# Power_Board_Schematic_Bad.net
KiCad netlist of a schematic drawn in Altium Designer
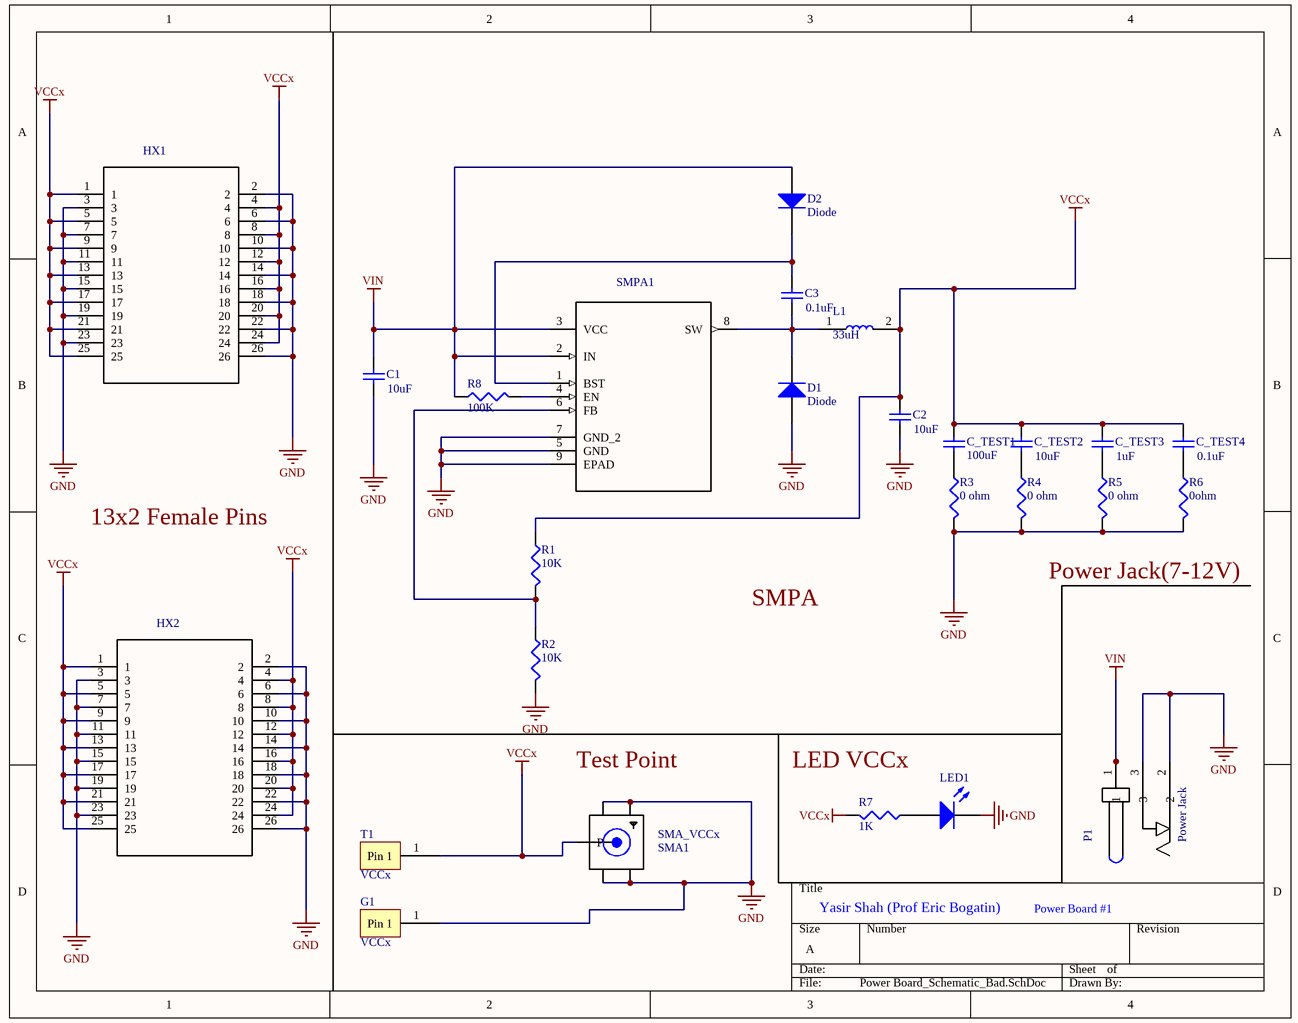
[diagram p0: Power Board_Schematic_Bad.SchDoc]

(export (version "E")
  (design (tool "Eeschema 10.0.6"))
  (components
    (comp (ref "C1")
      (value "10uF")
      (footprint "CAPC2012X140N")
      (description "Capacitor (Semiconductor SIM Model)")
      (fields (field (name "Comment") "Cap Semi") (field (name "PUBLISHER") "Altium Limited"))
      (libsource (lib "Miscellaneous Devices") (part "Cap Semi"))
    )
    (comp (ref "C2")
      (value "10uF")
      (footprint "CAPC2012X140N")
      (description "Capacitor (Semiconductor SIM Model)")
      (fields (field (name "Comment") "Cap Semi") (field (name "PUBLISHER") "Altium Limited"))
      (libsource (lib "Miscellaneous Devices") (part "Cap Semi"))
    )
    (comp (ref "C3")
      (value "0.1uF")
      (footprint "CAPC2012X140N")
      (description "Capacitor (Semiconductor SIM Model)")
      (fields (field (name "Comment") "Cap Semi") (field (name "PUBLISHER") "Altium Limited"))
      (libsource (lib "Miscellaneous Devices") (part "Cap Semi"))
    )
    (comp (ref "C_TEST1")
      (value "100uF")
      (footprint "CAPC2012X140N")
      (description "Capacitor (Semiconductor SIM Model)")
      (fields (field (name "Comment") "Cap Semi") (field (name "PUBLISHER") "Altium Limited"))
      (libsource (lib "Miscellaneous Devices") (part "Cap Semi"))
    )
    (comp (ref "C_TEST2")
      (value "10uF")
      (footprint "CAPC2012X140N")
      (description "Capacitor (Semiconductor SIM Model)")
      (fields (field (name "Comment") "Cap Semi") (field (name "PUBLISHER") "Altium Limited"))
      (libsource (lib "Miscellaneous Devices") (part "Cap Semi"))
    )
    (comp (ref "C_TEST3")
      (value "1uF")
      (footprint "CAPC2012X140N")
      (description "Capacitor (Semiconductor SIM Model)")
      (fields (field (name "Comment") "Cap Semi") (field (name "PUBLISHER") "Altium Limited"))
      (libsource (lib "Miscellaneous Devices") (part "Cap Semi"))
    )
    (comp (ref "C_TEST4")
      (value "0.1uF")
      (footprint "CAPC2012X140N")
      (description "Capacitor (Semiconductor SIM Model)")
      (fields (field (name "Comment") "Cap Semi") (field (name "PUBLISHER") "Altium Limited"))
      (libsource (lib "Miscellaneous Devices") (part "Cap Semi"))
    )
    (comp (ref "D1")
      (value "Diode")
      (footprint "D1")
      (description "Default Diode")
      (fields (field (name "PUBLISHER") "Altium Limited"))
      (libsource (lib "Miscellaneous Devices") (part "Diode"))
    )
    (comp (ref "D2")
      (value "Diode")
      (footprint "d2")
      (description "Default Diode")
      (fields (field (name "PUBLISHER") "Altium Limited"))
      (libsource (lib "Miscellaneous Devices") (part "Diode"))
    )
    (comp (ref "G1")
      (value "VCCx")
      (footprint "PCBComponent_1")
      (libsource (lib "SchematicLibrary") (part "1Pin Header"))
    )
    (comp (ref "HX1")
      (value "~")
      (footprint "TYCO_1761606-9")
      (description "Header, Pin, Idc, Amp-Latch, 26 Pos, Low Profile, Pcb, Vertical, Black")
      (fields (field (name "MF") "TE Connectivity") (field (name "MP") "1761606-9"))
      (libsource (lib "1761606-9") (part "1761606-9"))
    )
    (comp (ref "HX2")
      (value "~")
      (footprint "TYCO_1761606-9")
      (description "Header, Pin, Idc, Amp-Latch, 26 Pos, Low Profile, Pcb, Vertical, Black")
      (fields (field (name "MF") "TE Connectivity") (field (name "MP") "1761606-9"))
      (libsource (lib "1761606-9") (part "1761606-9"))
    )
    (comp (ref "L1")
      (value "33uH")
      (footprint "CAPC2012X140N")
      (description "Inductor Power Shielded Multi-Layer 2.2uH 20% 2MHz Ferrite 1A 195mOhm DCR 0805 Punched Paper T/R")
      (fields (field (name "MF") "TDK") (field (name "MP") "MLP2012H2R2MT0S1"))
      (libsource (lib "MLP2012H2R2MT0S1") (part "MLP2012H2R2MT0S1"))
    )
    (comp (ref "LED1")
      (value "LED2")
      (footprint "C1206")
      (description "Typical RED, GREEN, YELLOW, AMBER GaAs LED")
      (fields (field (name "PUBLISHER") "Altium Limited"))
      (libsource (lib "Miscellaneous Devices") (part "LED2"))
    )
    (comp (ref "P1")
      (value "Power Jack")
      (footprint "CUI_PJ-002AH-SMT-TR")
      (description "24 VDC 5 A Surface Mount Unshielded 2 Conductors 3 Contacts Male Power Jack")
      (fields (field (name "MF") "CUI") (field (name "MP") "PJ-002AH-SMT-TR"))
      (libsource (lib "PJ-002AH-SMT-TR") (part "PJ-002AH-SMT-TR"))
    )
    (comp (ref "R1")
      (value "10K")
      (footprint "RESC2012X70")
      (description "Resistor")
      (fields (field (name "Comment") "Res3") (field (name "PUBLISHER") "Altium Limited"))
      (libsource (lib "Miscellaneous Devices") (part "Res3"))
    )
    (comp (ref "R2")
      (value "10K")
      (footprint "RESC2012X70")
      (description "Resistor")
      (fields (field (name "Comment") "Res3") (field (name "PUBLISHER") "Altium Limited"))
      (libsource (lib "Miscellaneous Devices") (part "Res3"))
    )
    (comp (ref "R3")
      (value "0 ohm")
      (footprint "RESC3216X65")
      (description "Resistor")
      (fields (field (name "PUBLISHER") "Altium Limited"))
      (libsource (lib "Miscellaneous Devices") (part "Res3"))
    )
    (comp (ref "R4")
      (value "0 ohm")
      (footprint "RESC3216X65")
      (description "Resistor")
      (fields (field (name "PUBLISHER") "Altium Limited"))
      (libsource (lib "Miscellaneous Devices") (part "Res3"))
    )
    (comp (ref "R5")
      (value "0 ohm")
      (footprint "RESC3216X65")
      (description "Resistor")
      (fields (field (name "PUBLISHER") "Altium Limited"))
      (libsource (lib "Miscellaneous Devices") (part "Res3"))
    )
    (comp (ref "R6")
      (value "0ohm")
      (footprint "RESC3216X65")
      (description "Resistor")
      (fields (field (name "PUBLISHER") "Altium Limited"))
      (libsource (lib "Miscellaneous Devices") (part "Res3"))
    )
    (comp (ref "R7")
      (value "1K")
      (footprint "RESC2012X70")
      (description "Resistor")
      (fields (field (name "Comment") "Res3") (field (name "PUBLISHER") "Altium Limited"))
      (libsource (lib "Miscellaneous Devices") (part "Res3"))
    )
    (comp (ref "R8")
      (value "100K")
      (footprint "RESC2012X70")
      (description "Resistor")
      (fields (field (name "Comment") "Res3") (field (name "PUBLISHER") "Altium Limited"))
      (libsource (lib "Miscellaneous Devices") (part "Res3"))
    )
    (comp (ref "SMA_VCCx")
      (value "SMA1")
      (footprint "ADAFRUIT_1865_1865(Primary)")
      (description "Edge-Launch SMA Connector for 1.6mm / 0.062 Thick PCBs")
      (fields (field (name "MP") "1865") (field (name "MF") "Keystone"))
      (libsource (lib "1865") (part "1865"))
    )
    (comp (ref "SMPA1")
      (value "~")
      (footprint "SOP65P490X110-9N")
      (description "Swx Reg, Step d, Dc-Dc, 1.5a, 8soic")
      (fields (field (name "MF") "Texas Instruments") (field (name "MP") "LM2738XMY"))
      (libsource (lib "LM2738XMY") (part "LM2738XMY"))
    )
    (comp (ref "T1")
      (value "VCCx")
      (footprint "PCBComponent_1")
      (libsource (lib "SchematicLibrary") (part "1Pin Header"))
    )
  )
  (nets
    (net (code "1") (name "GND") (class "Default")
      (node (ref "C1") (pin "1") (pinfunction "1_1") (pintype "passive"))
      (node (ref "C2") (pin "1") (pinfunction "1_1") (pintype "passive"))
      (node (ref "D1") (pin "1") (pinfunction "A_1") (pintype "passive"))
      (node (ref "G1") (pin "1") (pinfunction "Pin_1_1") (pintype "passive"))
      (node (ref "HX1") (pin "10") (pinfunction "10_10") (pintype "passive"))
      (node (ref "HX1") (pin "11") (pinfunction "11_11") (pintype "passive"))
      (node (ref "HX1") (pin "14") (pinfunction "14_14") (pintype "passive"))
      (node (ref "HX1") (pin "15") (pinfunction "15_15") (pintype "passive"))
      (node (ref "HX1") (pin "18") (pinfunction "18_18") (pintype "passive"))
      (node (ref "HX1") (pin "19") (pinfunction "19_19") (pintype "passive"))
      (node (ref "HX1") (pin "2") (pinfunction "2_2") (pintype "passive"))
      (node (ref "HX1") (pin "22") (pinfunction "22_22") (pintype "passive"))
      (node (ref "HX1") (pin "23") (pinfunction "23_23") (pintype "passive"))
      (node (ref "HX1") (pin "26") (pinfunction "26_26") (pintype "passive"))
      (node (ref "HX1") (pin "3") (pinfunction "3_3") (pintype "passive"))
      (node (ref "HX1") (pin "6") (pinfunction "6_6") (pintype "passive"))
      (node (ref "HX1") (pin "7") (pinfunction "7_7") (pintype "passive"))
      (node (ref "HX2") (pin "10") (pinfunction "10_10") (pintype "passive"))
      (node (ref "HX2") (pin "11") (pinfunction "11_11") (pintype "passive"))
      (node (ref "HX2") (pin "14") (pinfunction "14_14") (pintype "passive"))
      (node (ref "HX2") (pin "15") (pinfunction "15_15") (pintype "passive"))
      (node (ref "HX2") (pin "18") (pinfunction "18_18") (pintype "passive"))
      (node (ref "HX2") (pin "19") (pinfunction "19_19") (pintype "passive"))
      (node (ref "HX2") (pin "2") (pinfunction "2_2") (pintype "passive"))
      (node (ref "HX2") (pin "22") (pinfunction "22_22") (pintype "passive"))
      (node (ref "HX2") (pin "23") (pinfunction "23_23") (pintype "passive"))
      (node (ref "HX2") (pin "26") (pinfunction "26_26") (pintype "passive"))
      (node (ref "HX2") (pin "3") (pinfunction "3_3") (pintype "passive"))
      (node (ref "HX2") (pin "6") (pinfunction "6_6") (pintype "passive"))
      (node (ref "HX2") (pin "7") (pinfunction "7_7") (pintype "passive"))
      (node (ref "LED1") (pin "2") (pinfunction "K_2") (pintype "passive"))
      (node (ref "P1") (pin "2") (pinfunction "2_2") (pintype "passive"))
      (node (ref "P1") (pin "3") (pinfunction "3_3") (pintype "passive"))
      (node (ref "R2") (pin "2") (pinfunction "2_2") (pintype "passive"))
      (node (ref "R3") (pin "2") (pinfunction "2_2") (pintype "passive"))
      (node (ref "R4") (pin "2") (pinfunction "2_2") (pintype "passive"))
      (node (ref "R5") (pin "2") (pinfunction "2_2") (pintype "passive"))
      (node (ref "R6") (pin "2") (pinfunction "2_2") (pintype "passive"))
      (node (ref "SMA_VCCx") (pin "GND1") (pinfunction "GND1_GND1") (pintype "power_in"))
      (node (ref "SMA_VCCx") (pin "GND2") (pinfunction "GND2_GND2") (pintype "power_in"))
      (node (ref "SMA_VCCx") (pin "GND3") (pinfunction "GND3_GND3") (pintype "power_in"))
      (node (ref "SMA_VCCx") (pin "GND4") (pinfunction "GND4_GND4") (pintype "power_in"))
      (node (ref "SMPA1") (pin "5") (pinfunction "GND_5") (pintype "passive"))
      (node (ref "SMPA1") (pin "7") (pinfunction "GND_2_7") (pintype "passive"))
      (node (ref "SMPA1") (pin "9") (pinfunction "EPAD_9") (pintype "passive"))
    )
    (net (code "2") (name "Net-(C_TEST1-Pad2)") (class "Default")
      (node (ref "C_TEST1") (pin "2") (pinfunction "2_2") (pintype "passive"))
      (node (ref "R3") (pin "1") (pinfunction "1_1") (pintype "passive"))
    )
    (net (code "3") (name "Net-(C_TEST2-Pad1)") (class "Default")
      (node (ref "C_TEST2") (pin "1") (pinfunction "1_1") (pintype "passive"))
      (node (ref "R4") (pin "1") (pinfunction "1_1") (pintype "passive"))
    )
    (net (code "4") (name "Net-(C_TEST3-Pad1)") (class "Default")
      (node (ref "C_TEST3") (pin "1") (pinfunction "1_1") (pintype "passive"))
      (node (ref "R5") (pin "1") (pinfunction "1_1") (pintype "passive"))
    )
    (net (code "5") (name "Net-(C_TEST4-Pad1)") (class "Default")
      (node (ref "C_TEST4") (pin "1") (pinfunction "1_1") (pintype "passive"))
      (node (ref "R6") (pin "1") (pinfunction "1_1") (pintype "passive"))
    )
    (net (code "6") (name "Net-(D1-K)") (class "Default")
      (node (ref "C3") (pin "1") (pinfunction "1_1") (pintype "passive"))
      (node (ref "D1") (pin "2") (pinfunction "K_2") (pintype "passive"))
      (node (ref "L1") (pin "1") (pinfunction "1_1") (pintype "passive"))
      (node (ref "SMPA1") (pin "8") (pinfunction "SW_8") (pintype "output"))
    )
    (net (code "7") (name "Net-(D2-K)") (class "Default")
      (node (ref "C3") (pin "2") (pinfunction "2_2") (pintype "passive"))
      (node (ref "D2") (pin "2") (pinfunction "K_2") (pintype "passive"))
      (node (ref "SMPA1") (pin "1") (pinfunction "BST_1") (pintype "input"))
    )
    (net (code "8") (name "Net-(LED1-A)") (class "Default")
      (node (ref "LED1") (pin "1") (pinfunction "A_1") (pintype "passive"))
      (node (ref "R7") (pin "1") (pinfunction "1_1") (pintype "passive"))
    )
    (net (code "9") (name "Net-(SMPA1-EN)") (class "Default")
      (node (ref "R8") (pin "2") (pinfunction "2_2") (pintype "passive"))
      (node (ref "SMPA1") (pin "4") (pinfunction "EN_4") (pintype "input"))
    )
    (net (code "10") (name "Net-(SMPA1-FB)") (class "Default")
      (node (ref "R1") (pin "2") (pinfunction "2_2") (pintype "passive"))
      (node (ref "R2") (pin "1") (pinfunction "1_1") (pintype "passive"))
      (node (ref "SMPA1") (pin "6") (pinfunction "FB_6") (pintype "input"))
    )
    (net (code "11") (name "VCCx") (class "Default")
      (node (ref "C2") (pin "2") (pinfunction "2_2") (pintype "passive"))
      (node (ref "C_TEST1") (pin "1") (pinfunction "1_1") (pintype "passive"))
      (node (ref "C_TEST2") (pin "2") (pinfunction "2_2") (pintype "passive"))
      (node (ref "C_TEST3") (pin "2") (pinfunction "2_2") (pintype "passive"))
      (node (ref "C_TEST4") (pin "2") (pinfunction "2_2") (pintype "passive"))
      (node (ref "HX1") (pin "1") (pinfunction "1_1") (pintype "passive"))
      (node (ref "HX1") (pin "12") (pinfunction "12_12") (pintype "passive"))
      (node (ref "HX1") (pin "13") (pinfunction "13_13") (pintype "passive"))
      (node (ref "HX1") (pin "16") (pinfunction "16_16") (pintype "passive"))
      (node (ref "HX1") (pin "17") (pinfunction "17_17") (pintype "passive"))
      (node (ref "HX1") (pin "20") (pinfunction "20_20") (pintype "passive"))
      (node (ref "HX1") (pin "21") (pinfunction "21_21") (pintype "passive"))
      (node (ref "HX1") (pin "24") (pinfunction "24_24") (pintype "passive"))
      (node (ref "HX1") (pin "25") (pinfunction "25_25") (pintype "passive"))
      (node (ref "HX1") (pin "4") (pinfunction "4_4") (pintype "passive"))
      (node (ref "HX1") (pin "5") (pinfunction "5_5") (pintype "passive"))
      (node (ref "HX1") (pin "8") (pinfunction "8_8") (pintype "passive"))
      (node (ref "HX1") (pin "9") (pinfunction "9_9") (pintype "passive"))
      (node (ref "HX2") (pin "1") (pinfunction "1_1") (pintype "passive"))
      (node (ref "HX2") (pin "12") (pinfunction "12_12") (pintype "passive"))
      (node (ref "HX2") (pin "13") (pinfunction "13_13") (pintype "passive"))
      (node (ref "HX2") (pin "16") (pinfunction "16_16") (pintype "passive"))
      (node (ref "HX2") (pin "17") (pinfunction "17_17") (pintype "passive"))
      (node (ref "HX2") (pin "20") (pinfunction "20_20") (pintype "passive"))
      (node (ref "HX2") (pin "21") (pinfunction "21_21") (pintype "passive"))
      (node (ref "HX2") (pin "24") (pinfunction "24_24") (pintype "passive"))
      (node (ref "HX2") (pin "25") (pinfunction "25_25") (pintype "passive"))
      (node (ref "HX2") (pin "4") (pinfunction "4_4") (pintype "passive"))
      (node (ref "HX2") (pin "5") (pinfunction "5_5") (pintype "passive"))
      (node (ref "HX2") (pin "8") (pinfunction "8_8") (pintype "passive"))
      (node (ref "HX2") (pin "9") (pinfunction "9_9") (pintype "passive"))
      (node (ref "L1") (pin "2") (pinfunction "2_2") (pintype "passive"))
      (node (ref "R1") (pin "1") (pinfunction "1_1") (pintype "passive"))
      (node (ref "R7") (pin "2") (pinfunction "2_2") (pintype "passive"))
      (node (ref "SMA_VCCx") (pin "P") (pinfunction "P_P") (pintype "bidirectional"))
      (node (ref "T1") (pin "1") (pinfunction "Pin_1_1") (pintype "passive"))
    )
    (net (code "12") (name "VIN") (class "Default")
      (node (ref "C1") (pin "2") (pinfunction "2_2") (pintype "passive"))
      (node (ref "D2") (pin "1") (pinfunction "A_1") (pintype "passive"))
      (node (ref "P1") (pin "1") (pinfunction "1_1") (pintype "passive"))
      (node (ref "R8") (pin "1") (pinfunction "1_1") (pintype "passive"))
      (node (ref "SMPA1") (pin "2") (pinfunction "IN_2") (pintype "input"))
      (node (ref "SMPA1") (pin "3") (pinfunction "VCC_3") (pintype "power_in"))
    )
  )
)
